# m1-data-register-a.net
KiCad netlist of a schematic drawn in EAGLE
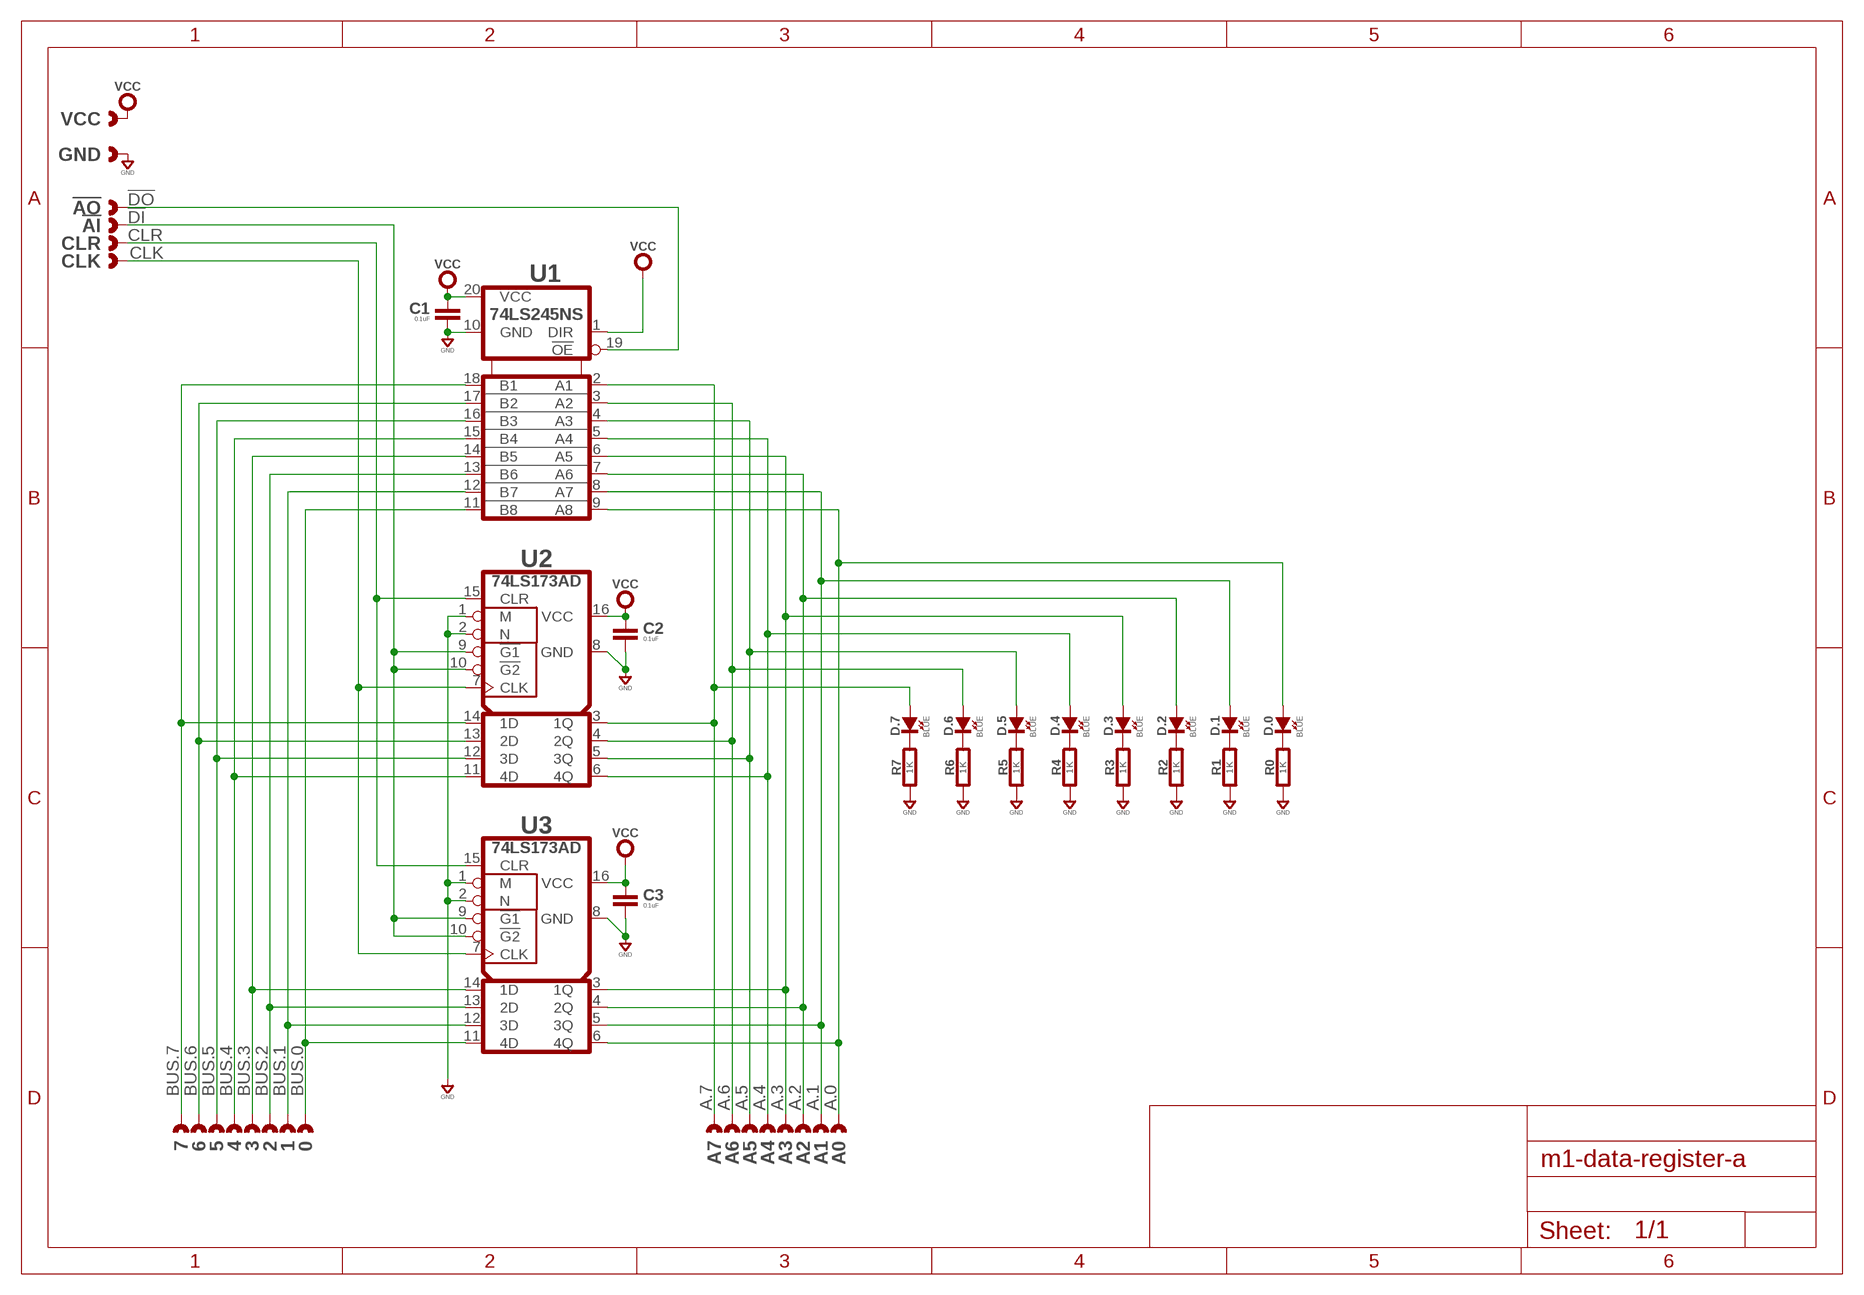
[diagram p0: schematic, sheet 1]

(export (version "E")
  (design (tool "Eeschema 10.0.6"))
  (components
    (comp (ref "!AI")
      (value "CAST-01X1")
      (footprint "eagle-import:CAST01-2.54MM")
      (libsource (lib "eagle-import") (part "CAST-01X1"))
    )
    (comp (ref "!AO")
      (value "CAST-01X1")
      (footprint "eagle-import:CAST01-2.54MM")
      (libsource (lib "eagle-import") (part "CAST-01X1"))
    )
    (comp (ref "0")
      (value "CAST-01X1")
      (footprint "eagle-import:CAST01-2.54MM")
      (libsource (lib "eagle-import") (part "CAST-01X1"))
    )
    (comp (ref "1")
      (value "CAST-01X1")
      (footprint "eagle-import:CAST01-2.54MM")
      (libsource (lib "eagle-import") (part "CAST-01X1"))
    )
    (comp (ref "2")
      (value "CAST-01X1")
      (footprint "eagle-import:CAST01-2.54MM")
      (libsource (lib "eagle-import") (part "CAST-01X1"))
    )
    (comp (ref "3")
      (value "CAST-01X1")
      (footprint "eagle-import:CAST01-2.54MM")
      (libsource (lib "eagle-import") (part "CAST-01X1"))
    )
    (comp (ref "4")
      (value "CAST-01X1")
      (footprint "eagle-import:CAST01-2.54MM")
      (libsource (lib "eagle-import") (part "CAST-01X1"))
    )
    (comp (ref "5")
      (value "CAST-01X1")
      (footprint "eagle-import:CAST01-2.54MM")
      (libsource (lib "eagle-import") (part "CAST-01X1"))
    )
    (comp (ref "6")
      (value "CAST-01X1")
      (footprint "eagle-import:CAST01-2.54MM")
      (libsource (lib "eagle-import") (part "CAST-01X1"))
    )
    (comp (ref "7")
      (value "CAST-01X1")
      (footprint "eagle-import:CAST01-2.54MM")
      (libsource (lib "eagle-import") (part "CAST-01X1"))
    )
    (comp (ref "A0")
      (value "CAST-01X1")
      (footprint "eagle-import:CAST01-2.54MM")
      (libsource (lib "eagle-import") (part "CAST-01X1"))
    )
    (comp (ref "A1")
      (value "CAST-01X1")
      (footprint "eagle-import:CAST01-2.54MM")
      (libsource (lib "eagle-import") (part "CAST-01X1"))
    )
    (comp (ref "A2")
      (value "CAST-01X1")
      (footprint "eagle-import:CAST01-2.54MM")
      (libsource (lib "eagle-import") (part "CAST-01X1"))
    )
    (comp (ref "A3")
      (value "CAST-01X1")
      (footprint "eagle-import:CAST01-2.54MM")
      (libsource (lib "eagle-import") (part "CAST-01X1"))
    )
    (comp (ref "A4")
      (value "CAST-01X1")
      (footprint "eagle-import:CAST01-2.54MM")
      (libsource (lib "eagle-import") (part "CAST-01X1"))
    )
    (comp (ref "A5")
      (value "CAST-01X1")
      (footprint "eagle-import:CAST01-2.54MM")
      (libsource (lib "eagle-import") (part "CAST-01X1"))
    )
    (comp (ref "A6")
      (value "CAST-01X1")
      (footprint "eagle-import:CAST01-2.54MM")
      (libsource (lib "eagle-import") (part "CAST-01X1"))
    )
    (comp (ref "A7")
      (value "CAST-01X1")
      (footprint "eagle-import:CAST01-2.54MM")
      (libsource (lib "eagle-import") (part "CAST-01X1"))
    )
    (comp (ref "C1")
      (value "0.1uF")
      (footprint "eagle-import:0603-CAP")
      (libsource (lib "eagle-import") (part "CAPACITOR0603"))
    )
    (comp (ref "C2")
      (value "0.1uF")
      (footprint "eagle-import:0603-CAP")
      (libsource (lib "eagle-import") (part "CAPACITOR0603"))
    )
    (comp (ref "C3")
      (value "0.1uF")
      (footprint "eagle-import:0603-CAP")
      (libsource (lib "eagle-import") (part "CAPACITOR0603"))
    )
    (comp (ref "CLK")
      (value "CAST-01X1")
      (footprint "eagle-import:CAST01-2.54MM")
      (libsource (lib "eagle-import") (part "CAST-01X1"))
    )
    (comp (ref "CLR")
      (value "CAST-01X1")
      (footprint "eagle-import:CAST01-2.54MM")
      (libsource (lib "eagle-import") (part "CAST-01X1"))
    )
    (comp (ref "D.0")
      (value "BLUE")
      (footprint "eagle-import:SMD_0603")
      (libsource (lib "eagle-import") (part "SMT0603"))
    )
    (comp (ref "D.1")
      (value "BLUE")
      (footprint "eagle-import:SMD_0603")
      (libsource (lib "eagle-import") (part "SMT0603"))
    )
    (comp (ref "D.2")
      (value "BLUE")
      (footprint "eagle-import:SMD_0603")
      (libsource (lib "eagle-import") (part "SMT0603"))
    )
    (comp (ref "D.3")
      (value "BLUE")
      (footprint "eagle-import:SMD_0603")
      (libsource (lib "eagle-import") (part "SMT0603"))
    )
    (comp (ref "D.4")
      (value "BLUE")
      (footprint "eagle-import:SMD_0603")
      (libsource (lib "eagle-import") (part "SMT0603"))
    )
    (comp (ref "D.5")
      (value "BLUE")
      (footprint "eagle-import:SMD_0603")
      (libsource (lib "eagle-import") (part "SMT0603"))
    )
    (comp (ref "D.6")
      (value "BLUE")
      (footprint "eagle-import:SMD_0603")
      (libsource (lib "eagle-import") (part "SMT0603"))
    )
    (comp (ref "D.7")
      (value "BLUE")
      (footprint "eagle-import:SMD_0603")
      (libsource (lib "eagle-import") (part "SMT0603"))
    )
    (comp (ref "GND")
      (value "CAST-01X1")
      (footprint "eagle-import:CAST01-2.54MM")
      (libsource (lib "eagle-import") (part "CAST-01X1"))
    )
    (comp (ref "R0")
      (value "1K")
      (footprint "eagle-import:0603-RES")
      (libsource (lib "eagle-import") (part "RESISTOR0603"))
    )
    (comp (ref "R1")
      (value "1K")
      (footprint "eagle-import:0603-RES")
      (libsource (lib "eagle-import") (part "RESISTOR0603"))
    )
    (comp (ref "R2")
      (value "1K")
      (footprint "eagle-import:0603-RES")
      (libsource (lib "eagle-import") (part "RESISTOR0603"))
    )
    (comp (ref "R3")
      (value "1K")
      (footprint "eagle-import:0603-RES")
      (libsource (lib "eagle-import") (part "RESISTOR0603"))
    )
    (comp (ref "R4")
      (value "1K")
      (footprint "eagle-import:0603-RES")
      (libsource (lib "eagle-import") (part "RESISTOR0603"))
    )
    (comp (ref "R5")
      (value "1K")
      (footprint "eagle-import:0603-RES")
      (libsource (lib "eagle-import") (part "RESISTOR0603"))
    )
    (comp (ref "R6")
      (value "1K")
      (footprint "eagle-import:0603-RES")
      (libsource (lib "eagle-import") (part "RESISTOR0603"))
    )
    (comp (ref "R7")
      (value "1K")
      (footprint "eagle-import:0603-RES")
      (libsource (lib "eagle-import") (part "RESISTOR0603"))
    )
    (comp (ref "U1")
      (value "74LS245NS")
      (footprint "eagle-import:SO20")
      (libsource (lib "eagle-import") (part "74245?NSLS"))
    )
    (comp (ref "U2")
      (value "74LS173AD")
      (footprint "eagle-import:SO16")
      (libsource (lib "eagle-import") (part "74173A?DLS"))
    )
    (comp (ref "U3")
      (value "74LS173AD")
      (footprint "eagle-import:SO16")
      (libsource (lib "eagle-import") (part "74173A?DLS"))
    )
    (comp (ref "VCC")
      (value "CAST-01X1")
      (footprint "eagle-import:CAST01-2.54MM")
      (libsource (lib "eagle-import") (part "CAST-01X1"))
    )
  )
  (nets
    (net (code "1") (name "/A.0") (class "Default")
      (node (ref "A0") (pin "1") (pinfunction "1_1") (pintype "bidirectional"))
      (node (ref "D.0") (pin "A") (pinfunction "A_A") (pintype "passive"))
      (node (ref "U1") (pin "9") (pinfunction "A8_9") (pintype "bidirectional"))
      (node (ref "U3") (pin "6") (pinfunction "4Q_6") (pintype "bidirectional"))
    )
    (net (code "2") (name "/A.1") (class "Default")
      (node (ref "A1") (pin "1") (pinfunction "1_1") (pintype "bidirectional"))
      (node (ref "D.1") (pin "A") (pinfunction "A_A") (pintype "passive"))
      (node (ref "U1") (pin "8") (pinfunction "A7_8") (pintype "bidirectional"))
      (node (ref "U3") (pin "5") (pinfunction "3Q_5") (pintype "bidirectional"))
    )
    (net (code "3") (name "/A.2") (class "Default")
      (node (ref "A2") (pin "1") (pinfunction "1_1") (pintype "bidirectional"))
      (node (ref "D.2") (pin "A") (pinfunction "A_A") (pintype "passive"))
      (node (ref "U1") (pin "7") (pinfunction "A6_7") (pintype "bidirectional"))
      (node (ref "U3") (pin "4") (pinfunction "2Q_4") (pintype "bidirectional"))
    )
    (net (code "4") (name "/A.3") (class "Default")
      (node (ref "A3") (pin "1") (pinfunction "1_1") (pintype "bidirectional"))
      (node (ref "D.3") (pin "A") (pinfunction "A_A") (pintype "passive"))
      (node (ref "U1") (pin "6") (pinfunction "A5_6") (pintype "bidirectional"))
      (node (ref "U3") (pin "3") (pinfunction "1Q_3") (pintype "bidirectional"))
    )
    (net (code "5") (name "/A.4") (class "Default")
      (node (ref "A4") (pin "1") (pinfunction "1_1") (pintype "bidirectional"))
      (node (ref "D.4") (pin "A") (pinfunction "A_A") (pintype "passive"))
      (node (ref "U1") (pin "5") (pinfunction "A4_5") (pintype "bidirectional"))
      (node (ref "U2") (pin "6") (pinfunction "4Q_6") (pintype "bidirectional"))
    )
    (net (code "6") (name "/A.5") (class "Default")
      (node (ref "A5") (pin "1") (pinfunction "1_1") (pintype "bidirectional"))
      (node (ref "D.5") (pin "A") (pinfunction "A_A") (pintype "passive"))
      (node (ref "U1") (pin "4") (pinfunction "A3_4") (pintype "bidirectional"))
      (node (ref "U2") (pin "5") (pinfunction "3Q_5") (pintype "bidirectional"))
    )
    (net (code "7") (name "/A.6") (class "Default")
      (node (ref "A6") (pin "1") (pinfunction "1_1") (pintype "bidirectional"))
      (node (ref "D.6") (pin "A") (pinfunction "A_A") (pintype "passive"))
      (node (ref "U1") (pin "3") (pinfunction "A2_3") (pintype "bidirectional"))
      (node (ref "U2") (pin "4") (pinfunction "2Q_4") (pintype "bidirectional"))
    )
    (net (code "8") (name "/A.7") (class "Default")
      (node (ref "A7") (pin "1") (pinfunction "1_1") (pintype "bidirectional"))
      (node (ref "D.7") (pin "A") (pinfunction "A_A") (pintype "passive"))
      (node (ref "U1") (pin "2") (pinfunction "A1_2") (pintype "bidirectional"))
      (node (ref "U2") (pin "3") (pinfunction "1Q_3") (pintype "bidirectional"))
    )
    (net (code "9") (name "/BUS.0") (class "Default")
      (node (ref "0") (pin "1") (pinfunction "1_1") (pintype "bidirectional"))
      (node (ref "U1") (pin "11") (pinfunction "B8_11") (pintype "bidirectional"))
      (node (ref "U3") (pin "11") (pinfunction "4D_11") (pintype "bidirectional"))
    )
    (net (code "10") (name "/BUS.1") (class "Default")
      (node (ref "1") (pin "1") (pinfunction "1_1") (pintype "bidirectional"))
      (node (ref "U1") (pin "12") (pinfunction "B7_12") (pintype "bidirectional"))
      (node (ref "U3") (pin "12") (pinfunction "3D_12") (pintype "bidirectional"))
    )
    (net (code "11") (name "/BUS.2") (class "Default")
      (node (ref "2") (pin "1") (pinfunction "1_1") (pintype "bidirectional"))
      (node (ref "U1") (pin "13") (pinfunction "B6_13") (pintype "bidirectional"))
      (node (ref "U3") (pin "13") (pinfunction "2D_13") (pintype "bidirectional"))
    )
    (net (code "12") (name "/BUS.3") (class "Default")
      (node (ref "3") (pin "1") (pinfunction "1_1") (pintype "bidirectional"))
      (node (ref "U1") (pin "14") (pinfunction "B5_14") (pintype "bidirectional"))
      (node (ref "U3") (pin "14") (pinfunction "1D_14") (pintype "bidirectional"))
    )
    (net (code "13") (name "/BUS.4") (class "Default")
      (node (ref "4") (pin "1") (pinfunction "1_1") (pintype "bidirectional"))
      (node (ref "U1") (pin "15") (pinfunction "B4_15") (pintype "bidirectional"))
      (node (ref "U2") (pin "11") (pinfunction "4D_11") (pintype "bidirectional"))
    )
    (net (code "14") (name "/BUS.5") (class "Default")
      (node (ref "5") (pin "1") (pinfunction "1_1") (pintype "bidirectional"))
      (node (ref "U1") (pin "16") (pinfunction "B3_16") (pintype "bidirectional"))
      (node (ref "U2") (pin "12") (pinfunction "3D_12") (pintype "bidirectional"))
    )
    (net (code "15") (name "/BUS.6") (class "Default")
      (node (ref "6") (pin "1") (pinfunction "1_1") (pintype "bidirectional"))
      (node (ref "U1") (pin "17") (pinfunction "B2_17") (pintype "bidirectional"))
      (node (ref "U2") (pin "13") (pinfunction "2D_13") (pintype "bidirectional"))
    )
    (net (code "16") (name "/BUS.7") (class "Default")
      (node (ref "7") (pin "1") (pinfunction "1_1") (pintype "bidirectional"))
      (node (ref "U1") (pin "18") (pinfunction "B1_18") (pintype "bidirectional"))
      (node (ref "U2") (pin "14") (pinfunction "1D_14") (pintype "bidirectional"))
    )
    (net (code "17") (name "/CLK") (class "Default")
      (node (ref "CLK") (pin "1") (pinfunction "1_1") (pintype "bidirectional"))
      (node (ref "U2") (pin "7") (pinfunction "CLK_7") (pintype "bidirectional"))
      (node (ref "U3") (pin "7") (pinfunction "CLK_7") (pintype "bidirectional"))
    )
    (net (code "18") (name "/CLR") (class "Default")
      (node (ref "CLR") (pin "1") (pinfunction "1_1") (pintype "bidirectional"))
      (node (ref "U2") (pin "15") (pinfunction "CLR_15") (pintype "bidirectional"))
      (node (ref "U3") (pin "15") (pinfunction "CLR_15") (pintype "bidirectional"))
    )
    (net (code "19") (name "/~{DI}") (class "Default")
      (node (ref "!AI") (pin "1") (pinfunction "1_1") (pintype "bidirectional"))
      (node (ref "U2") (pin "10") (pinfunction "~{G2}_10") (pintype "bidirectional"))
      (node (ref "U2") (pin "9") (pinfunction "~{G1}_9") (pintype "bidirectional"))
      (node (ref "U3") (pin "10") (pinfunction "~{G2}_10") (pintype "bidirectional"))
      (node (ref "U3") (pin "9") (pinfunction "~{G1}_9") (pintype "bidirectional"))
    )
    (net (code "20") (name "/~{DO}") (class "Default")
      (node (ref "!AO") (pin "1") (pinfunction "1_1") (pintype "bidirectional"))
      (node (ref "U1") (pin "19") (pinfunction "~{OE}_19") (pintype "bidirectional"))
    )
    (net (code "21") (name "GND") (class "Default")
      (node (ref "C1") (pin "2") (pinfunction "2_2") (pintype "passive"))
      (node (ref "C2") (pin "2") (pinfunction "2_2") (pintype "passive"))
      (node (ref "C3") (pin "2") (pinfunction "2_2") (pintype "passive"))
      (node (ref "GND") (pin "1") (pinfunction "1_1") (pintype "bidirectional"))
      (node (ref "R0") (pin "1") (pinfunction "1_1") (pintype "passive"))
      (node (ref "R1") (pin "1") (pinfunction "1_1") (pintype "passive"))
      (node (ref "R2") (pin "1") (pinfunction "1_1") (pintype "passive"))
      (node (ref "R3") (pin "1") (pinfunction "1_1") (pintype "passive"))
      (node (ref "R4") (pin "1") (pinfunction "1_1") (pintype "passive"))
      (node (ref "R5") (pin "1") (pinfunction "1_1") (pintype "passive"))
      (node (ref "R6") (pin "1") (pinfunction "1_1") (pintype "passive"))
      (node (ref "R7") (pin "1") (pinfunction "1_1") (pintype "passive"))
      (node (ref "U1") (pin "10") (pinfunction "GND_10") (pintype "bidirectional"))
      (node (ref "U2") (pin "1") (pinfunction "M_1") (pintype "bidirectional"))
      (node (ref "U2") (pin "2") (pinfunction "N_2") (pintype "bidirectional"))
      (node (ref "U2") (pin "8") (pinfunction "GND_8") (pintype "bidirectional"))
      (node (ref "U3") (pin "1") (pinfunction "M_1") (pintype "bidirectional"))
      (node (ref "U3") (pin "2") (pinfunction "N_2") (pintype "bidirectional"))
      (node (ref "U3") (pin "8") (pinfunction "GND_8") (pintype "bidirectional"))
    )
    (net (code "22") (name "Net-(D.0-C)") (class "Default")
      (node (ref "D.0") (pin "K") (pinfunction "C_K") (pintype "passive"))
      (node (ref "R0") (pin "2") (pinfunction "2_2") (pintype "passive"))
    )
    (net (code "23") (name "Net-(D.1-C)") (class "Default")
      (node (ref "D.1") (pin "K") (pinfunction "C_K") (pintype "passive"))
      (node (ref "R1") (pin "2") (pinfunction "2_2") (pintype "passive"))
    )
    (net (code "24") (name "Net-(D.2-C)") (class "Default")
      (node (ref "D.2") (pin "K") (pinfunction "C_K") (pintype "passive"))
      (node (ref "R2") (pin "2") (pinfunction "2_2") (pintype "passive"))
    )
    (net (code "25") (name "Net-(D.3-C)") (class "Default")
      (node (ref "D.3") (pin "K") (pinfunction "C_K") (pintype "passive"))
      (node (ref "R3") (pin "2") (pinfunction "2_2") (pintype "passive"))
    )
    (net (code "26") (name "Net-(D.4-C)") (class "Default")
      (node (ref "D.4") (pin "K") (pinfunction "C_K") (pintype "passive"))
      (node (ref "R4") (pin "2") (pinfunction "2_2") (pintype "passive"))
    )
    (net (code "27") (name "Net-(D.5-C)") (class "Default")
      (node (ref "D.5") (pin "K") (pinfunction "C_K") (pintype "passive"))
      (node (ref "R5") (pin "2") (pinfunction "2_2") (pintype "passive"))
    )
    (net (code "28") (name "Net-(D.6-C)") (class "Default")
      (node (ref "D.6") (pin "K") (pinfunction "C_K") (pintype "passive"))
      (node (ref "R6") (pin "2") (pinfunction "2_2") (pintype "passive"))
    )
    (net (code "29") (name "Net-(D.7-C)") (class "Default")
      (node (ref "D.7") (pin "K") (pinfunction "C_K") (pintype "passive"))
      (node (ref "R7") (pin "2") (pinfunction "2_2") (pintype "passive"))
    )
    (net (code "30") (name "VCC") (class "Default")
      (node (ref "C1") (pin "1") (pinfunction "1_1") (pintype "passive"))
      (node (ref "C2") (pin "1") (pinfunction "1_1") (pintype "passive"))
      (node (ref "C3") (pin "1") (pinfunction "1_1") (pintype "passive"))
      (node (ref "U1") (pin "1") (pinfunction "DIR_1") (pintype "bidirectional"))
      (node (ref "U1") (pin "20") (pinfunction "VCC_20") (pintype "bidirectional"))
      (node (ref "U2") (pin "16") (pinfunction "VCC_16") (pintype "bidirectional"))
      (node (ref "U3") (pin "16") (pinfunction "VCC_16") (pintype "bidirectional"))
      (node (ref "VCC") (pin "1") (pinfunction "1_1") (pintype "bidirectional"))
    )
  )
)
